# 2_FPGA.net
KiCad netlist of a schematic drawn in Altium Designer
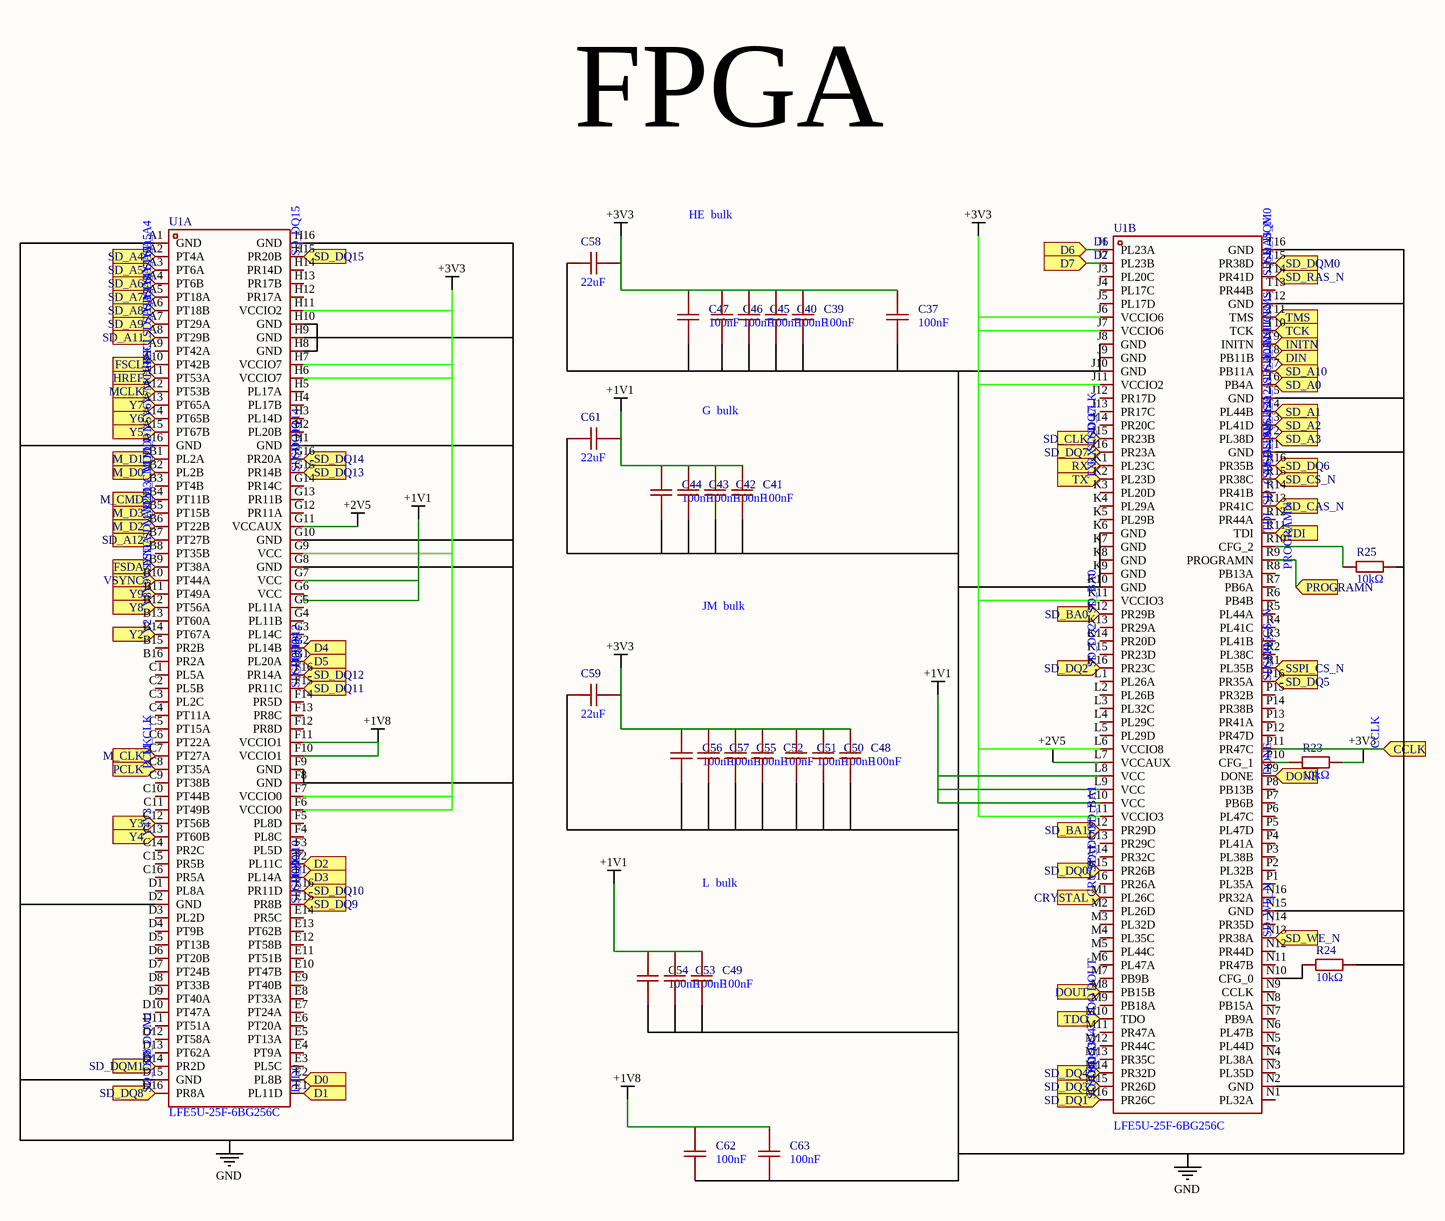
[diagram p0: 2_FPGA.schdoc]

(export (version "E")
  (design (tool "Eeschema 10.0.6"))
  (components
    (comp (ref "C37")
      (value "100nF")
      (footprint "C01005")
      (fields
        (field (name "MANUFACTURER") "muRata(村田)")
        (field (name "MANUFACTURER PART") "GRM022R60J104KE15D")
        (field (name "TOLERANCE") "±10%")
      )
      (libsource (lib "altium-import") (part "root_2_GRM022R60J104KE15D_"))
    )
    (comp (ref "C39")
      (value "100nF")
      (footprint "C01005")
      (fields
        (field (name "MANUFACTURER") "muRata(村田)")
        (field (name "MANUFACTURER PART") "GRM022R60J104KE15D")
        (field (name "TOLERANCE") "±10%")
      )
      (libsource (lib "altium-import") (part "root_2_GRM022R60J104KE15D_"))
    )
    (comp (ref "C40")
      (value "100nF")
      (footprint "C01005")
      (fields
        (field (name "MANUFACTURER") "muRata(村田)")
        (field (name "MANUFACTURER PART") "GRM022R60J104KE15D")
        (field (name "TOLERANCE") "±10%")
      )
      (libsource (lib "altium-import") (part "root_2_GRM022R60J104KE15D_"))
    )
    (comp (ref "C41")
      (value "100nF")
      (footprint "C01005")
      (fields
        (field (name "MANUFACTURER") "muRata(村田)")
        (field (name "MANUFACTURER PART") "GRM022R60J104KE15D")
        (field (name "TOLERANCE") "±10%")
      )
      (libsource (lib "altium-import") (part "root_2_GRM022R60J104KE15D_"))
    )
    (comp (ref "C42")
      (value "100nF")
      (footprint "C01005")
      (fields
        (field (name "MANUFACTURER") "muRata(村田)")
        (field (name "MANUFACTURER PART") "GRM022R60J104KE15D")
        (field (name "TOLERANCE") "±10%")
      )
      (libsource (lib "altium-import") (part "root_2_GRM022R60J104KE15D_"))
    )
    (comp (ref "C43")
      (value "100nF")
      (footprint "C01005")
      (fields
        (field (name "MANUFACTURER") "muRata(村田)")
        (field (name "MANUFACTURER PART") "GRM022R60J104KE15D")
        (field (name "TOLERANCE") "±10%")
      )
      (libsource (lib "altium-import") (part "root_2_GRM022R60J104KE15D_"))
    )
    (comp (ref "C44")
      (value "100nF")
      (footprint "C01005")
      (fields
        (field (name "MANUFACTURER") "muRata(村田)")
        (field (name "MANUFACTURER PART") "GRM022R60J104KE15D")
        (field (name "TOLERANCE") "±10%")
      )
      (libsource (lib "altium-import") (part "root_2_GRM022R60J104KE15D_"))
    )
    (comp (ref "C45")
      (value "100nF")
      (footprint "C01005")
      (fields
        (field (name "MANUFACTURER") "muRata(村田)")
        (field (name "MANUFACTURER PART") "GRM022R60J104KE15D")
        (field (name "TOLERANCE") "±10%")
      )
      (libsource (lib "altium-import") (part "root_2_GRM022R60J104KE15D_"))
    )
    (comp (ref "C46")
      (value "100nF")
      (footprint "C01005")
      (fields
        (field (name "MANUFACTURER") "muRata(村田)")
        (field (name "MANUFACTURER PART") "GRM022R60J104KE15D")
        (field (name "TOLERANCE") "±10%")
      )
      (libsource (lib "altium-import") (part "root_2_GRM022R60J104KE15D_"))
    )
    (comp (ref "C47")
      (value "100nF")
      (footprint "C01005")
      (fields
        (field (name "MANUFACTURER") "muRata(村田)")
        (field (name "MANUFACTURER PART") "GRM022R60J104KE15D")
        (field (name "TOLERANCE") "±10%")
      )
      (libsource (lib "altium-import") (part "root_2_GRM022R60J104KE15D_"))
    )
    (comp (ref "C48")
      (value "100nF")
      (footprint "C01005")
      (fields
        (field (name "MANUFACTURER") "muRata(村田)")
        (field (name "MANUFACTURER PART") "GRM022R60J104KE15D")
        (field (name "TOLERANCE") "±10%")
      )
      (libsource (lib "altium-import") (part "root_2_GRM022R60J104KE15D_"))
    )
    (comp (ref "C49")
      (value "100nF")
      (footprint "C01005")
      (fields
        (field (name "MANUFACTURER") "muRata(村田)")
        (field (name "MANUFACTURER PART") "GRM022R60J104KE15D")
        (field (name "TOLERANCE") "±10%")
      )
      (libsource (lib "altium-import") (part "root_2_GRM022R60J104KE15D_"))
    )
    (comp (ref "C50")
      (value "100nF")
      (footprint "C01005")
      (fields
        (field (name "MANUFACTURER") "muRata(村田)")
        (field (name "MANUFACTURER PART") "GRM022R60J104KE15D")
        (field (name "TOLERANCE") "±10%")
      )
      (libsource (lib "altium-import") (part "root_2_GRM022R60J104KE15D_"))
    )
    (comp (ref "C51")
      (value "100nF")
      (footprint "C01005")
      (fields
        (field (name "MANUFACTURER") "muRata(村田)")
        (field (name "MANUFACTURER PART") "GRM022R60J104KE15D")
        (field (name "TOLERANCE") "±10%")
      )
      (libsource (lib "altium-import") (part "root_2_GRM022R60J104KE15D_"))
    )
    (comp (ref "C52")
      (value "100nF")
      (footprint "C01005")
      (fields
        (field (name "MANUFACTURER") "muRata(村田)")
        (field (name "MANUFACTURER PART") "GRM022R60J104KE15D")
        (field (name "TOLERANCE") "±10%")
      )
      (libsource (lib "altium-import") (part "root_2_GRM022R60J104KE15D_"))
    )
    (comp (ref "C53")
      (value "100nF")
      (footprint "C01005")
      (fields
        (field (name "MANUFACTURER") "muRata(村田)")
        (field (name "MANUFACTURER PART") "GRM022R60J104KE15D")
        (field (name "TOLERANCE") "±10%")
      )
      (libsource (lib "altium-import") (part "root_2_GRM022R60J104KE15D_"))
    )
    (comp (ref "C54")
      (value "100nF")
      (footprint "C01005")
      (fields
        (field (name "MANUFACTURER") "muRata(村田)")
        (field (name "MANUFACTURER PART") "GRM022R60J104KE15D")
        (field (name "TOLERANCE") "±10%")
      )
      (libsource (lib "altium-import") (part "root_2_GRM022R60J104KE15D_"))
    )
    (comp (ref "C55")
      (value "100nF")
      (footprint "C01005")
      (fields
        (field (name "MANUFACTURER") "muRata(村田)")
        (field (name "MANUFACTURER PART") "GRM022R60J104KE15D")
        (field (name "TOLERANCE") "±10%")
      )
      (libsource (lib "altium-import") (part "root_2_GRM022R60J104KE15D_"))
    )
    (comp (ref "C56")
      (value "100nF")
      (footprint "C01005")
      (fields
        (field (name "MANUFACTURER") "muRata(村田)")
        (field (name "MANUFACTURER PART") "GRM022R60J104KE15D")
        (field (name "TOLERANCE") "±10%")
      )
      (libsource (lib "altium-import") (part "root_2_GRM022R60J104KE15D_"))
    )
    (comp (ref "C57")
      (value "100nF")
      (footprint "C01005")
      (fields
        (field (name "MANUFACTURER") "muRata(村田)")
        (field (name "MANUFACTURER PART") "GRM022R60J104KE15D")
        (field (name "TOLERANCE") "±10%")
      )
      (libsource (lib "altium-import") (part "root_2_GRM022R60J104KE15D_"))
    )
    (comp (ref "C58")
      (value "22uF")
      (footprint "C0603")
      (fields
        (field (name "MANUFACTURER") "CCTC(三环)")
        (field (name "MANUFACTURER PART") "TCC0603X5R226M6R3CT")
        (field (name "TOLERANCE") "±20%")
      )
      (libsource (lib "altium-import") (part "root_1_TCC0603X5R226M6R3CT_"))
    )
    (comp (ref "C59")
      (value "22uF")
      (footprint "C0603")
      (fields
        (field (name "MANUFACTURER") "CCTC(三环)")
        (field (name "MANUFACTURER PART") "TCC0603X5R226M6R3CT")
        (field (name "TOLERANCE") "±20%")
      )
      (libsource (lib "altium-import") (part "root_1_TCC0603X5R226M6R3CT_"))
    )
    (comp (ref "C61")
      (value "22uF")
      (footprint "C0603")
      (fields
        (field (name "MANUFACTURER") "CCTC(三环)")
        (field (name "MANUFACTURER PART") "TCC0603X5R226M6R3CT")
        (field (name "TOLERANCE") "±20%")
      )
      (libsource (lib "altium-import") (part "root_1_TCC0603X5R226M6R3CT_"))
    )
    (comp (ref "C62")
      (value "100nF")
      (footprint "C01005")
      (fields
        (field (name "MANUFACTURER") "muRata(村田)")
        (field (name "MANUFACTURER PART") "GRM022R60J104KE15D")
        (field (name "TOLERANCE") "±10%")
      )
      (libsource (lib "altium-import") (part "root_2_GRM022R60J104KE15D_"))
    )
    (comp (ref "C63")
      (value "100nF")
      (footprint "C01005")
      (fields
        (field (name "MANUFACTURER") "muRata(村田)")
        (field (name "MANUFACTURER PART") "GRM022R60J104KE15D")
        (field (name "TOLERANCE") "±10%")
      )
      (libsource (lib "altium-import") (part "root_2_GRM022R60J104KE15D_"))
    )
    (comp (ref "R23")
      (value "10kΩ")
      (footprint "R0402")
      (fields
        (field (name "MANUFACTURER") "UNI-ROYAL(厚声)")
        (field (name "MANUFACTURER PART") "0402WGF1002TCE")
        (field (name "TOLERANCE") "±1%")
      )
      (libsource (lib "altium-import") (part "root_2_0402WGF1002TCE_"))
    )
    (comp (ref "R24")
      (value "10kΩ")
      (footprint "R0402")
      (fields
        (field (name "MANUFACTURER") "UNI-ROYAL(厚声)")
        (field (name "MANUFACTURER PART") "0402WGF1002TCE")
        (field (name "TOLERANCE") "±1%")
      )
      (libsource (lib "altium-import") (part "root_2_0402WGF1002TCE_"))
    )
    (comp (ref "R25")
      (value "10kΩ")
      (footprint "R0402")
      (fields
        (field (name "MANUFACTURER") "UNI-ROYAL(厚声)")
        (field (name "MANUFACTURER PART") "0402WGF1002TCE")
        (field (name "TOLERANCE") "±1%")
      )
      (libsource (lib "altium-import") (part "root_2_0402WGF1002TCE_"))
    )
    (comp (ref "U1")
      (value "LFE5U-25F-6BG256C")
      (footprint "CABGA-256_L14.0-W14.0-R16-C16-P0.80-TL")
      (fields (field (name "MANUFACTURER") "LATTICE(莱迪思)"))
      (libsource (lib "altium-import") (part "root_0_LFE5U-25F-6BG256C_"))
    )
  )
  (nets
    (net (code "1") (name "+1V1") (class "Default")
      (node (ref "C41") (pin "1") (pinfunction "1_1") (pintype "passive"))
      (node (ref "C42") (pin "1") (pinfunction "1_1") (pintype "passive"))
      (node (ref "C43") (pin "1") (pinfunction "1_1") (pintype "passive"))
      (node (ref "C44") (pin "1") (pinfunction "1_1") (pintype "passive"))
      (node (ref "C49") (pin "1") (pinfunction "1_1") (pintype "passive"))
      (node (ref "C53") (pin "1") (pinfunction "1_1") (pintype "passive"))
      (node (ref "C54") (pin "1") (pinfunction "1_1") (pintype "passive"))
      (node (ref "C61") (pin "1") (pinfunction "1_1") (pintype "passive"))
      (node (ref "U1") (pin "G6") (pinfunction "VCC_G6") (pintype "passive"))
      (node (ref "U1") (pin "G7") (pinfunction "VCC_G7") (pintype "passive"))
      (node (ref "U1") (pin "L10") (pinfunction "VCC_L10") (pintype "passive"))
      (node (ref "U1") (pin "L8") (pinfunction "VCC_L8") (pintype "passive"))
      (node (ref "U1") (pin "L9") (pinfunction "VCC_L9") (pintype "passive"))
    )
    (net (code "2") (name "+1V8") (class "Default")
      (node (ref "C62") (pin "1") (pinfunction "1_1") (pintype "passive"))
      (node (ref "C63") (pin "1") (pinfunction "1_1") (pintype "passive"))
      (node (ref "U1") (pin "F10") (pinfunction "VCCIO1_F10") (pintype "passive"))
      (node (ref "U1") (pin "F11") (pinfunction "VCCIO1_F11") (pintype "passive"))
    )
    (net (code "3") (name "+2V5") (class "Default")
      (node (ref "U1") (pin "G11") (pinfunction "VCCAUX_G11") (pintype "passive"))
      (node (ref "U1") (pin "L7") (pinfunction "VCCAUX_L7") (pintype "passive"))
    )
    (net (code "4") (name "+3V3") (class "Default")
      (node (ref "C37") (pin "1") (pinfunction "1_1") (pintype "passive"))
      (node (ref "C39") (pin "1") (pinfunction "1_1") (pintype "passive"))
      (node (ref "C40") (pin "1") (pinfunction "1_1") (pintype "passive"))
      (node (ref "C45") (pin "1") (pinfunction "1_1") (pintype "passive"))
      (node (ref "C46") (pin "1") (pinfunction "1_1") (pintype "passive"))
      (node (ref "C47") (pin "1") (pinfunction "1_1") (pintype "passive"))
      (node (ref "C48") (pin "1") (pinfunction "1_1") (pintype "passive"))
      (node (ref "C50") (pin "1") (pinfunction "1_1") (pintype "passive"))
      (node (ref "C51") (pin "1") (pinfunction "1_1") (pintype "passive"))
      (node (ref "C52") (pin "1") (pinfunction "1_1") (pintype "passive"))
      (node (ref "C55") (pin "1") (pinfunction "1_1") (pintype "passive"))
      (node (ref "C56") (pin "1") (pinfunction "1_1") (pintype "passive"))
      (node (ref "C57") (pin "1") (pinfunction "1_1") (pintype "passive"))
      (node (ref "C58") (pin "1") (pinfunction "1_1") (pintype "passive"))
      (node (ref "C59") (pin "1") (pinfunction "1_1") (pintype "passive"))
      (node (ref "R23") (pin "1") (pinfunction "1_1") (pintype "passive"))
      (node (ref "U1") (pin "F6") (pinfunction "VCCIO0_F6") (pintype "passive"))
      (node (ref "U1") (pin "F7") (pinfunction "VCCIO0_F7") (pintype "passive"))
      (node (ref "U1") (pin "G9") (pinfunction "VCC_G9") (pintype "passive"))
      (node (ref "U1") (pin "H11") (pinfunction "VCCIO2_H11") (pintype "passive"))
      (node (ref "U1") (pin "H6") (pinfunction "VCCIO7_H6") (pintype "passive"))
      (node (ref "U1") (pin "H7") (pinfunction "VCCIO7_H7") (pintype "passive"))
      (node (ref "U1") (pin "J11") (pinfunction "VCCIO2_J11") (pintype "passive"))
      (node (ref "U1") (pin "J6") (pinfunction "VCCIO6_J6") (pintype "passive"))
      (node (ref "U1") (pin "J7") (pinfunction "VCCIO6_J7") (pintype "passive"))
      (node (ref "U1") (pin "K11") (pinfunction "VCCIO3_K11") (pintype "passive"))
      (node (ref "U1") (pin "L11") (pinfunction "VCCIO3_L11") (pintype "passive"))
      (node (ref "U1") (pin "L6") (pinfunction "VCCIO8_L6") (pintype "passive"))
    )
    (net (code "5") (name "/CCLK") (class "Default")
      (node (ref "U1") (pin "P11") (pinfunction "PR47C_P11") (pintype "passive"))
    )
    (net (code "6") (name "/CRYSTAL") (class "Default")
      (node (ref "U1") (pin "M1") (pinfunction "PL26C_M1") (pintype "passive"))
    )
    (net (code "7") (name "/D0") (class "Default")
      (node (ref "U1") (pin "E2") (pinfunction "PL8B_E2") (pintype "passive"))
    )
    (net (code "8") (name "/D1") (class "Default")
      (node (ref "U1") (pin "E1") (pinfunction "PL11D_E1") (pintype "passive"))
    )
    (net (code "9") (name "/D2") (class "Default")
      (node (ref "U1") (pin "F2") (pinfunction "PL11C_F2") (pintype "passive"))
    )
    (net (code "10") (name "/D3") (class "Default")
      (node (ref "U1") (pin "F1") (pinfunction "PL14A_F1") (pintype "passive"))
    )
    (net (code "11") (name "/D4") (class "Default")
      (node (ref "U1") (pin "G2") (pinfunction "PL14B_G2") (pintype "passive"))
    )
    (net (code "12") (name "/D5") (class "Default")
      (node (ref "U1") (pin "G1") (pinfunction "PL20A_G1") (pintype "passive"))
    )
    (net (code "13") (name "/D6") (class "Default")
      (node (ref "U1") (pin "J1") (pinfunction "PL23A_J1") (pintype "passive"))
    )
    (net (code "14") (name "/D7") (class "Default")
      (node (ref "U1") (pin "J2") (pinfunction "PL23B_J2") (pintype "passive"))
    )
    (net (code "15") (name "/DIN") (class "Default")
      (node (ref "U1") (pin "T8") (pinfunction "PB11B_T8") (pintype "passive"))
    )
    (net (code "16") (name "/DONE") (class "Default")
      (node (ref "U1") (pin "P9") (pinfunction "DONE_P9") (pintype "passive"))
    )
    (net (code "17") (name "/DOUT") (class "Default")
      (node (ref "U1") (pin "M8") (pinfunction "PB15B_M8") (pintype "passive"))
    )
    (net (code "18") (name "/FSCL") (class "Default")
      (node (ref "U1") (pin "A10") (pinfunction "PT42B_A10") (pintype "passive"))
    )
    (net (code "19") (name "/FSDA") (class "Default")
      (node (ref "U1") (pin "B9") (pinfunction "PT38A_B9") (pintype "passive"))
    )
    (net (code "20") (name "/HREF") (class "Default")
      (node (ref "U1") (pin "A11") (pinfunction "PT53A_A11") (pintype "passive"))
    )
    (net (code "21") (name "/INITN") (class "Default")
      (node (ref "U1") (pin "T9") (pinfunction "INITN_T9") (pintype "passive"))
    )
    (net (code "22") (name "/MCLK") (class "Default")
      (node (ref "U1") (pin "A12") (pinfunction "PT53B_A12") (pintype "passive"))
    )
    (net (code "23") (name "/M_CLK") (class "Default")
      (node (ref "U1") (pin "C7") (pinfunction "PT27A_C7") (pintype "passive"))
    )
    (net (code "24") (name "/M_CMD") (class "Default")
      (node (ref "U1") (pin "B4") (pinfunction "PT11B_B4") (pintype "passive"))
    )
    (net (code "25") (name "/M_D0") (class "Default")
      (node (ref "U1") (pin "B2") (pinfunction "PL2B_B2") (pintype "passive"))
    )
    (net (code "26") (name "/M_D1") (class "Default")
      (node (ref "U1") (pin "B1") (pinfunction "PL2A_B1") (pintype "passive"))
    )
    (net (code "27") (name "/M_D2") (class "Default")
      (node (ref "U1") (pin "B6") (pinfunction "PT22B_B6") (pintype "passive"))
    )
    (net (code "28") (name "/M_D3") (class "Default")
      (node (ref "U1") (pin "B5") (pinfunction "PT15B_B5") (pintype "passive"))
    )
    (net (code "29") (name "/PCLK") (class "Default")
      (node (ref "U1") (pin "C8") (pinfunction "PT35A_C8") (pintype "passive"))
    )
    (net (code "30") (name "/PROGRAMN") (class "Default")
      (node (ref "U1") (pin "R9") (pinfunction "PROGRAMN_R9") (pintype "passive"))
    )
    (net (code "31") (name "/RX") (class "Default")
      (node (ref "U1") (pin "K1") (pinfunction "PL23C_K1") (pintype "passive"))
    )
    (net (code "32") (name "/SD_A0") (class "Default")
      (node (ref "U1") (pin "T6") (pinfunction "PB4A_T6") (pintype "passive"))
    )
    (net (code "33") (name "/SD_A1") (class "Default")
      (node (ref "U1") (pin "T4") (pinfunction "PL44B_T4") (pintype "passive"))
    )
    (net (code "34") (name "/SD_A2") (class "Default")
      (node (ref "U1") (pin "T3") (pinfunction "PL41D_T3") (pintype "passive"))
    )
    (net (code "35") (name "/SD_A3") (class "Default")
      (node (ref "U1") (pin "T2") (pinfunction "PL38D_T2") (pintype "passive"))
    )
    (net (code "36") (name "/SD_A4") (class "Default")
      (node (ref "U1") (pin "A2") (pinfunction "PT4A_A2") (pintype "passive"))
    )
    (net (code "37") (name "/SD_A5") (class "Default")
      (node (ref "U1") (pin "A3") (pinfunction "PT6A_A3") (pintype "passive"))
    )
    (net (code "38") (name "/SD_A6") (class "Default")
      (node (ref "U1") (pin "A4") (pinfunction "PT6B_A4") (pintype "passive"))
    )
    (net (code "39") (name "/SD_A7") (class "Default")
      (node (ref "U1") (pin "A5") (pinfunction "PT18A_A5") (pintype "passive"))
    )
    (net (code "40") (name "/SD_A8") (class "Default")
      (node (ref "U1") (pin "A6") (pinfunction "PT18B_A6") (pintype "passive"))
    )
    (net (code "41") (name "/SD_A9") (class "Default")
      (node (ref "U1") (pin "A7") (pinfunction "PT29A_A7") (pintype "passive"))
    )
    (net (code "42") (name "/SD_A10") (class "Default")
      (node (ref "U1") (pin "T7") (pinfunction "PB11A_T7") (pintype "passive"))
    )
    (net (code "43") (name "/SD_A11") (class "Default")
      (node (ref "U1") (pin "A8") (pinfunction "PT29B_A8") (pintype "passive"))
    )
    (net (code "44") (name "/SD_A12") (class "Default")
      (node (ref "U1") (pin "B7") (pinfunction "PT27B_B7") (pintype "passive"))
    )
    (net (code "45") (name "/SD_BA0") (class "Default")
      (node (ref "U1") (pin "K12") (pinfunction "PR29B_K12") (pintype "passive"))
    )
    (net (code "46") (name "/SD_BA1") (class "Default")
      (node (ref "U1") (pin "L12") (pinfunction "PR29D_L12") (pintype "passive"))
    )
    (net (code "47") (name "/SD_CAS_N") (class "Default")
      (node (ref "U1") (pin "R13") (pinfunction "PR41C_R13") (pintype "passive"))
    )
    (net (code "48") (name "/SD_CLK") (class "Default")
      (node (ref "U1") (pin "J15") (pinfunction "PR23B_J15") (pintype "passive"))
    )
    (net (code "49") (name "/SD_CS_N") (class "Default")
      (node (ref "U1") (pin "R15") (pinfunction "PR38C_R15") (pintype "passive"))
    )
    (net (code "50") (name "/SD_DQ0") (class "Default")
      (node (ref "U1") (pin "L15") (pinfunction "PR26B_L15") (pintype "passive"))
    )
    (net (code "51") (name "/SD_DQ1") (class "Default")
      (node (ref "U1") (pin "M16") (pinfunction "PR26C_M16") (pintype "passive"))
    )
    (net (code "52") (name "/SD_DQ2") (class "Default")
      (node (ref "U1") (pin "K16") (pinfunction "PR23C_K16") (pintype "passive"))
    )
    (net (code "53") (name "/SD_DQ3") (class "Default")
      (node (ref "U1") (pin "M15") (pinfunction "PR26D_M15") (pintype "passive"))
    )
    (net (code "54") (name "/SD_DQ4") (class "Default")
      (node (ref "U1") (pin "M14") (pinfunction "PR32D_M14") (pintype "passive"))
    )
    (net (code "55") (name "/SD_DQ5") (class "Default")
      (node (ref "U1") (pin "P16") (pinfunction "PR35A_P16") (pintype "passive"))
    )
    (net (code "56") (name "/SD_DQ6") (class "Default")
      (node (ref "U1") (pin "R16") (pinfunction "PR35B_R16") (pintype "passive"))
    )
    (net (code "57") (name "/SD_DQ7") (class "Default")
      (node (ref "U1") (pin "J16") (pinfunction "PR23A_J16") (pintype "passive"))
    )
    (net (code "58") (name "/SD_DQ8") (class "Default")
      (node (ref "U1") (pin "D16") (pinfunction "PR8A_D16") (pintype "passive"))
    )
    (net (code "59") (name "/SD_DQ9") (class "Default")
      (node (ref "U1") (pin "E15") (pinfunction "PR8B_E15") (pintype "passive"))
    )
    (net (code "60") (name "/SD_DQ10") (class "Default")
      (node (ref "U1") (pin "E16") (pinfunction "PR11D_E16") (pintype "passive"))
    )
    (net (code "61") (name "/SD_DQ11") (class "Default")
      (node (ref "U1") (pin "F15") (pinfunction "PR11C_F15") (pintype "passive"))
    )
    (net (code "62") (name "/SD_DQ12") (class "Default")
      (node (ref "U1") (pin "F16") (pinfunction "PR14A_F16") (pintype "passive"))
    )
    (net (code "63") (name "/SD_DQ13") (class "Default")
      (node (ref "U1") (pin "G15") (pinfunction "PR14B_G15") (pintype "passive"))
    )
    (net (code "64") (name "/SD_DQ14") (class "Default")
      (node (ref "U1") (pin "G16") (pinfunction "PR20A_G16") (pintype "passive"))
    )
    (net (code "65") (name "/SD_DQ15") (class "Default")
      (node (ref "U1") (pin "H15") (pinfunction "PR20B_H15") (pintype "passive"))
    )
    (net (code "66") (name "/SD_DQM0") (class "Default")
      (node (ref "U1") (pin "T15") (pinfunction "PR38D_T15") (pintype "passive"))
    )
    (net (code "67") (name "/SD_DQM1") (class "Default")
      (node (ref "U1") (pin "D14") (pinfunction "PR2D_D14") (pintype "passive"))
    )
    (net (code "68") (name "/SD_RAS_N") (class "Default")
      (node (ref "U1") (pin "T14") (pinfunction "PR41D_T14") (pintype "passive"))
    )
    (net (code "69") (name "/SD_WE_N") (class "Default")
      (node (ref "U1") (pin "N13") (pinfunction "PR38A_N13") (pintype "passive"))
    )
    (net (code "70") (name "/SSPI_CS_N") (class "Default")
      (node (ref "U1") (pin "R1") (pinfunction "PL35B_R1") (pintype "passive"))
    )
    (net (code "71") (name "/TCK") (class "Default")
      (node (ref "U1") (pin "T10") (pinfunction "TCK_T10") (pintype "passive"))
    )
    (net (code "72") (name "/TDI") (class "Default")
      (node (ref "U1") (pin "R11") (pinfunction "TDI_R11") (pintype "passive"))
    )
    (net (code "73") (name "/TDO") (class "Default")
      (node (ref "U1") (pin "M10") (pinfunction "TDO_M10") (pintype "passive"))
    )
    (net (code "74") (name "/TMS") (class "Default")
      (node (ref "U1") (pin "T11") (pinfunction "TMS_T11") (pintype "passive"))
    )
    (net (code "75") (name "/TX") (class "Default")
      (node (ref "U1") (pin "K2") (pinfunction "PL23D_K2") (pintype "passive"))
    )
    (net (code "76") (name "/VSYNC") (class "Default")
      (node (ref "U1") (pin "B10") (pinfunction "PT44A_B10") (pintype "passive"))
    )
    (net (code "77") (name "/Y2") (class "Default")
      (node (ref "U1") (pin "B14") (pinfunction "PT67A_B14") (pintype "passive"))
    )
    (net (code "78") (name "/Y3") (class "Default")
      (node (ref "U1") (pin "C12") (pinfunction "PT56B_C12") (pintype "passive"))
    )
    (net (code "79") (name "/Y4") (class "Default")
      (node (ref "U1") (pin "C13") (pinfunction "PT60B_C13") (pintype "passive"))
    )
    (net (code "80") (name "/Y5") (class "Default")
      (node (ref "U1") (pin "A15") (pinfunction "PT67B_A15") (pintype "passive"))
    )
    (net (code "81") (name "/Y6") (class "Default")
      (node (ref "U1") (pin "A14") (pinfunction "PT65B_A14") (pintype "passive"))
    )
    (net (code "82") (name "/Y7") (class "Default")
      (node (ref "U1") (pin "A13") (pinfunction "PT65A_A13") (pintype "passive"))
    )
    (net (code "83") (name "/Y8") (class "Default")
      (node (ref "U1") (pin "B12") (pinfunction "PT56A_B12") (pintype "passive"))
    )
    (net (code "84") (name "/Y9") (class "Default")
      (node (ref "U1") (pin "B11") (pinfunction "PT49A_B11") (pintype "passive"))
    )
    (net (code "85") (name "GND") (class "Default")
      (node (ref "C37") (pin "2") (pinfunction "2_2") (pintype "passive"))
      (node (ref "C39") (pin "2") (pinfunction "2_2") (pintype "passive"))
      (node (ref "C40") (pin "2") (pinfunction "2_2") (pintype "passive"))
      (node (ref "C41") (pin "2") (pinfunction "2_2") (pintype "passive"))
      (node (ref "C42") (pin "2") (pinfunction "2_2") (pintype "passive"))
      (node (ref "C43") (pin "2") (pinfunction "2_2") (pintype "passive"))
      (node (ref "C44") (pin "2") (pinfunction "2_2") (pintype "passive"))
      (node (ref "C45") (pin "2") (pinfunction "2_2") (pintype "passive"))
      (node (ref "C46") (pin "2") (pinfunction "2_2") (pintype "passive"))
      (node (ref "C47") (pin "2") (pinfunction "2_2") (pintype "passive"))
      (node (ref "C48") (pin "2") (pinfunction "2_2") (pintype "passive"))
      (node (ref "C49") (pin "2") (pinfunction "2_2") (pintype "passive"))
      (node (ref "C50") (pin "2") (pinfunction "2_2") (pintype "passive"))
      (node (ref "C51") (pin "2") (pinfunction "2_2") (pintype "passive"))
      (node (ref "C52") (pin "2") (pinfunction "2_2") (pintype "passive"))
      (node (ref "C53") (pin "2") (pinfunction "2_2") (pintype "passive"))
      (node (ref "C54") (pin "2") (pinfunction "2_2") (pintype "passive"))
      (node (ref "C55") (pin "2") (pinfunction "2_2") (pintype "passive"))
      (node (ref "C56") (pin "2") (pinfunction "2_2") (pintype "passive"))
      (node (ref "C57") (pin "2") (pinfunction "2_2") (pintype "passive"))
      (node (ref "C58") (pin "2") (pinfunction "2_2") (pintype "passive"))
      (node (ref "C59") (pin "2") (pinfunction "2_2") (pintype "passive"))
      (node (ref "C61") (pin "2") (pinfunction "2_2") (pintype "passive"))
      (node (ref "C62") (pin "2") (pinfunction "2_2") (pintype "passive"))
      (node (ref "C63") (pin "2") (pinfunction "2_2") (pintype "passive"))
      (node (ref "R24") (pin "1") (pinfunction "1_1") (pintype "passive"))
      (node (ref "R25") (pin "1") (pinfunction "1_1") (pintype "passive"))
      (node (ref "U1") (pin "A1") (pinfunction "GND_A1") (pintype "passive"))
      (node (ref "U1") (pin "A16") (pinfunction "GND_A16") (pintype "passive"))
      (node (ref "U1") (pin "D15") (pinfunction "GND_D15") (pintype "passive"))
      (node (ref "U1") (pin "D2") (pinfunction "GND_D2") (pintype "passive"))
      (node (ref "U1") (pin "F8") (pinfunction "GND_F8") (pintype "passive"))
      (node (ref "U1") (pin "F9") (pinfunction "GND_F9") (pintype "passive"))
      (node (ref "U1") (pin "G10") (pinfunction "GND_G10") (pintype "passive"))
      (node (ref "U1") (pin "G8") (pinfunction "GND_G8") (pintype "passive"))
      (node (ref "U1") (pin "H1") (pinfunction "GND_H1") (pintype "passive"))
      (node (ref "U1") (pin "H10") (pinfunction "GND_H10") (pintype "passive"))
      (node (ref "U1") (pin "H16") (pinfunction "GND_H16") (pintype "passive"))
      (node (ref "U1") (pin "H8") (pinfunction "GND_H8") (pintype "passive"))
      (node (ref "U1") (pin "H9") (pinfunction "GND_H9") (pintype "passive"))
      (node (ref "U1") (pin "J10") (pinfunction "GND_J10") (pintype "passive"))
      (node (ref "U1") (pin "J8") (pinfunction "GND_J8") (pintype "passive"))
      (node (ref "U1") (pin "J9") (pinfunction "GND_J9") (pintype "passive"))
      (node (ref "U1") (pin "K10") (pinfunction "GND_K10") (pintype "passive"))
      (node (ref "U1") (pin "K6") (pinfunction "GND_K6") (pintype "passive"))
      (node (ref "U1") (pin "K7") (pinfunction "GND_K7") (pintype "passive"))
      (node (ref "U1") (pin "K8") (pinfunction "GND_K8") (pintype "passive"))
      (node (ref "U1") (pin "K9") (pinfunction "GND_K9") (pintype "passive"))
      (node (ref "U1") (pin "N15") (pinfunction "GND_N15") (pintype "passive"))
      (node (ref "U1") (pin "N2") (pinfunction "GND_N2") (pintype "passive"))
      (node (ref "U1") (pin "T1") (pinfunction "GND_T1") (pintype "passive"))
      (node (ref "U1") (pin "T12") (pinfunction "GND_T12") (pintype "passive"))
      (node (ref "U1") (pin "T16") (pinfunction "GND_T16") (pintype "passive"))
      (node (ref "U1") (pin "T5") (pinfunction "GND_T5") (pintype "passive"))
    )
    (net (code "86") (name "Net-(U1B-CFG_0)") (class "Default")
      (node (ref "R24") (pin "2") (pinfunction "2_2") (pintype "passive"))
      (node (ref "U1") (pin "N10") (pinfunction "CFG_0_N10") (pintype "passive"))
    )
    (net (code "87") (name "Net-(U1B-CFG_1)") (class "Default")
      (node (ref "R23") (pin "2") (pinfunction "2_2") (pintype "passive"))
      (node (ref "U1") (pin "P10") (pinfunction "CFG_1_P10") (pintype "passive"))
    )
    (net (code "88") (name "Net-(U1B-CFG_2)") (class "Default")
      (node (ref "R25") (pin "2") (pinfunction "2_2") (pintype "passive"))
      (node (ref "U1") (pin "R10") (pinfunction "CFG_2_R10") (pintype "passive"))
    )
    (net (code "89") (name "unconnected-(U1A-PL2C-PadC3)") (class "Default")
      (node (ref "U1") (pin "C3") (pinfunction "PL2C_C3") (pintype "passive"))
    )
    (net (code "90") (name "unconnected-(U1A-PL2D-PadD3)") (class "Default")
      (node (ref "U1") (pin "D3") (pinfunction "PL2D_D3") (pintype "passive"))
    )
    (net (code "91") (name "unconnected-(U1A-PL5A-PadC1)") (class "Default")
      (node (ref "U1") (pin "C1") (pinfunction "PL5A_C1") (pintype "passive"))
    )
    (net (code "92") (name "unconnected-(U1A-PL5B-PadC2)") (class "Default")
      (node (ref "U1") (pin "C2") (pinfunction "PL5B_C2") (pintype "passive"))
    )
    (net (code "93") (name "unconnected-(U1A-PL5C-PadE3)") (class "Default")
      (node (ref "U1") (pin "E3") (pinfunction "PL5C_E3") (pintype "passive"))
    )
    (net (code "94") (name "unconnected-(U1A-PL5D-PadF3)") (class "Default")
      (node (ref "U1") (pin "F3") (pinfunction "PL5D_F3") (pintype "passive"))
    )
    (net (code "95") (name "unconnected-(U1A-PL8A-PadD1)") (class "Default")
      (node (ref "U1") (pin "D1") (pinfunction "PL8A_D1") (pintype "passive"))
    )
    (net (code "96") (name "unconnected-(U1A-PL8C-PadF4)") (class "Default")
      (node (ref "U1") (pin "F4") (pinfunction "PL8C_F4") (pintype "passive"))
    )
    (net (code "97") (name "unconnected-(U1A-PL8D-PadF5)") (class "Default")
      (node (ref "U1") (pin "F5") (pinfunction "PL8D_F5") (pintype "passive"))
    )
    (net (code "98") (name "unconnected-(U1A-PL11A-PadG5)") (class "Default")
      (node (ref "U1") (pin "G5") (pinfunction "PL11A_G5") (pintype "passive"))
    )
    (net (code "99") (name "unconnected-(U1A-PL11B-PadG4)") (class "Default")
      (node (ref "U1") (pin "G4") (pinfunction "PL11B_G4") (pintype "passive"))
    )
    (net (code "100") (name "unconnected-(U1A-PL14C-PadG3)") (class "Default")
      (node (ref "U1") (pin "G3") (pinfunction "PL14C_G3") (pintype "passive"))
    )
    (net (code "101") (name "unconnected-(U1A-PL14D-PadH3)") (class "Default")
      (node (ref "U1") (pin "H3") (pinfunction "PL14D_H3") (pintype "passive"))
    )
    (net (code "102") (name "unconnected-(U1A-PL17A-PadH5)") (class "Default")
      (node (ref "U1") (pin "H5") (pinfunction "PL17A_H5") (pintype "passive"))
    )
    (net (code "103") (name "unconnected-(U1A-PL17B-PadH4)") (class "Default")
      (node (ref "U1") (pin "H4") (pinfunction "PL17B_H4") (pintype "passive"))
    )
    (net (code "104") (name "unconnected-(U1A-PL20B-PadH2)") (class "Default")
      (node (ref "U1") (pin "H2") (pinfunction "PL20B_H2") (pintype "passive"))
    )
    (net (code "105") (name "unconnected-(U1A-PR2A-PadB16)") (class "Default")
      (node (ref "U1") (pin "B16") (pinfunction "PR2A_B16") (pintype "passive"))
    )
    (net (code "106") (name "unconnected-(U1A-PR2B-PadB15)") (class "Default")
      (node (ref "U1") (pin "B15") (pinfunction "PR2B_B15") (pintype "passive"))
    )
    (net (code "107") (name "unconnected-(U1A-PR2C-PadC14)") (class "Default")
      (node (ref "U1") (pin "C14") (pinfunction "PR2C_C14") (pintype "passive"))
    )
    (net (code "108") (name "unconnected-(U1A-PR5A-PadC16)") (class "Default")
      (node (ref "U1") (pin "C16") (pinfunction "PR5A_C16") (pintype "passive"))
    )
    (net (code "109") (name "unconnected-(U1A-PR5B-PadC15)") (class "Default")
      (node (ref "U1") (pin "C15") (pinfunction "PR5B_C15") (pintype "passive"))
    )
    (net (code "110") (name "unconnected-(U1A-PR5C-PadE14)") (class "Default")
      (node (ref "U1") (pin "E14") (pinfunction "PR5C_E14") (pintype "passive"))
    )
    (net (code "111") (name "unconnected-(U1A-PR5D-PadF14)") (class "Default")
      (node (ref "U1") (pin "F14") (pinfunction "PR5D_F14") (pintype "passive"))
    )
    (net (code "112") (name "unconnected-(U1A-PR8C-PadF13)") (class "Default")
      (node (ref "U1") (pin "F13") (pinfunction "PR8C_F13") (pintype "passive"))
    )
    (net (code "113") (name "unconnected-(U1A-PR8D-PadF12)") (class "Default")
      (node (ref "U1") (pin "F12") (pinfunction "PR8D_F12") (pintype "passive"))
    )
    (net (code "114") (name "unconnected-(U1A-PR11A-PadG12)") (class "Default")
      (node (ref "U1") (pin "G12") (pinfunction "PR11A_G12") (pintype "passive"))
    )
    (net (code "115") (name "unconnected-(U1A-PR11B-PadG13)") (class "Default")
      (node (ref "U1") (pin "G13") (pinfunction "PR11B_G13") (pintype "passive"))
    )
    (net (code "116") (name "unconnected-(U1A-PR14C-PadG14)") (class "Default")
      (node (ref "U1") (pin "G14") (pinfunction "PR14C_G14") (pintype "passive"))
    )
    (net (code "117") (name "unconnected-(U1A-PR14D-PadH14)") (class "Default")
      (node (ref "U1") (pin "H14") (pinfunction "PR14D_H14") (pintype "passive"))
    )
    (net (code "118") (name "unconnected-(U1A-PR17A-PadH12)") (class "Default")
      (node (ref "U1") (pin "H12") (pinfunction "PR17A_H12") (pintype "passive"))
    )
    (net (code "119") (name "unconnected-(U1A-PR17B-PadH13)") (class "Default")
      (node (ref "U1") (pin "H13") (pinfunction "PR17B_H13") (pintype "passive"))
    )
    (net (code "120") (name "unconnected-(U1A-PT4B-PadB3)") (class "Default")
      (node (ref "U1") (pin "B3") (pinfunction "PT4B_B3") (pintype "passive"))
    )
    (net (code "121") (name "unconnected-(U1A-PT9A-PadE4)") (class "Default")
      (node (ref "U1") (pin "E4") (pinfunction "PT9A_E4") (pintype "passive"))
    )
    (net (code "122") (name "unconnected-(U1A-PT9B-PadD4)") (class "Default")
      (node (ref "U1") (pin "D4") (pinfunction "PT9B_D4") (pintype "passive"))
    )
    (net (code "123") (name "unconnected-(U1A-PT11A-PadC4)") (class "Default")
      (node (ref "U1") (pin "C4") (pinfunction "PT11A_C4") (pintype "passive"))
    )
    (net (code "124") (name "unconnected-(U1A-PT13A-PadE5)") (class "Default")
      (node (ref "U1") (pin "E5") (pinfunction "PT13A_E5") (pintype "passive"))
    )
    (net (code "125") (name "unconnected-(U1A-PT13B-PadD5)") (class "Default")
      (node (ref "U1") (pin "D5") (pinfunction "PT13B_D5") (pintype "passive"))
    )
    (net (code "126") (name "unconnected-(U1A-PT15A-PadC5)") (class "Default")
      (node (ref "U1") (pin "C5") (pinfunction "PT15A_C5") (pintype "passive"))
    )
    (net (code "127") (name "unconnected-(U1A-PT20A-PadE6)") (class "Default")
      (node (ref "U1") (pin "E6") (pinfunction "PT20A_E6") (pintype "passive"))
    )
    (net (code "128") (name "unconnected-(U1A-PT20B-PadD6)") (class "Default")
      (node (ref "U1") (pin "D6") (pinfunction "PT20B_D6") (pintype "passive"))
    )
    (net (code "129") (name "unconnected-(U1A-PT22A-PadC6)") (class "Default")
      (node (ref "U1") (pin "C6") (pinfunction "PT22A_C6") (pintype "passive"))
    )
    (net (code "130") (name "unconnected-(U1A-PT24A-PadE7)") (class "Default")
      (node (ref "U1") (pin "E7") (pinfunction "PT24A_E7") (pintype "passive"))
    )
    (net (code "131") (name "unconnected-(U1A-PT24B-PadD7)") (class "Default")
      (node (ref "U1") (pin "D7") (pinfunction "PT24B_D7") (pintype "passive"))
    )
    (net (code "132") (name "unconnected-(U1A-PT33A-PadE8)") (class "Default")
      (node (ref "U1") (pin "E8") (pinfunction "PT33A_E8") (pintype "passive"))
    )
    (net (code "133") (name "unconnected-(U1A-PT33B-PadD8)") (class "Default")
      (node (ref "U1") (pin "D8") (pinfunction "PT33B_D8") (pintype "passive"))
    )
    (net (code "134") (name "unconnected-(U1A-PT35B-PadB8)") (class "Default")
      (node (ref "U1") (pin "B8") (pinfunction "PT35B_B8") (pintype "passive"))
    )
    (net (code "135") (name "unconnected-(U1A-PT38B-PadC9)") (class "Default")
      (node (ref "U1") (pin "C9") (pinfunction "PT38B_C9") (pintype "passive"))
    )
    (net (code "136") (name "unconnected-(U1A-PT40A-PadD9)") (class "Default")
      (node (ref "U1") (pin "D9") (pinfunction "PT40A_D9") (pintype "passive"))
    )
    (net (code "137") (name "unconnected-(U1A-PT40B-PadE9)") (class "Default")
      (node (ref "U1") (pin "E9") (pinfunction "PT40B_E9") (pintype "passive"))
    )
    (net (code "138") (name "unconnected-(U1A-PT42A-PadA9)") (class "Default")
      (node (ref "U1") (pin "A9") (pinfunction "PT42A_A9") (pintype "passive"))
    )
    (net (code "139") (name "unconnected-(U1A-PT44B-PadC10)") (class "Default")
      (node (ref "U1") (pin "C10") (pinfunction "PT44B_C10") (pintype "passive"))
    )
    (net (code "140") (name "unconnected-(U1A-PT47A-PadD10)") (class "Default")
      (node (ref "U1") (pin "D10") (pinfunction "PT47A_D10") (pintype "passive"))
    )
    (net (code "141") (name "unconnected-(U1A-PT47B-PadE10)") (class "Default")
      (node (ref "U1") (pin "E10") (pinfunction "PT47B_E10") (pintype "passive"))
    )
    (net (code "142") (name "unconnected-(U1A-PT49B-PadC11)") (class "Default")
      (node (ref "U1") (pin "C11") (pinfunction "PT49B_C11") (pintype "passive"))
    )
    (net (code "143") (name "unconnected-(U1A-PT51A-PadD11)") (class "Default")
      (node (ref "U1") (pin "D11") (pinfunction "PT51A_D11") (pintype "passive"))
    )
    (net (code "144") (name "unconnected-(U1A-PT51B-PadE11)") (class "Default")
      (node (ref "U1") (pin "E11") (pinfunction "PT51B_E11") (pintype "passive"))
    )
    (net (code "145") (name "unconnected-(U1A-PT58A-PadD12)") (class "Default")
      (node (ref "U1") (pin "D12") (pinfunction "PT58A_D12") (pintype "passive"))
    )
    (net (code "146") (name "unconnected-(U1A-PT58B-PadE12)") (class "Default")
      (node (ref "U1") (pin "E12") (pinfunction "PT58B_E12") (pintype "passive"))
    )
    (net (code "147") (name "unconnected-(U1A-PT60A-PadB13)") (class "Default")
      (node (ref "U1") (pin "B13") (pinfunction "PT60A_B13") (pintype "passive"))
    )
    (net (code "148") (name "unconnected-(U1A-PT62A-PadD13)") (class "Default")
      (node (ref "U1") (pin "D13") (pinfunction "PT62A_D13") (pintype "passive"))
    )
    (net (code "149") (name "unconnected-(U1A-PT62B-PadE13)") (class "Default")
      (node (ref "U1") (pin "E13") (pinfunction "PT62B_E13") (pintype "passive"))
    )
    (net (code "150") (name "unconnected-(U1B-CCLK-PadN9)") (class "Default")
      (node (ref "U1") (pin "N9") (pinfunction "CCLK_N9") (pintype "passive"))
    )
    (net (code "151") (name "unconnected-(U1B-PB4B-PadR6)") (class "Default")
      (node (ref "U1") (pin "R6") (pinfunction "PB4B_R6") (pintype "passive"))
    )
    (net (code "152") (name "unconnected-(U1B-PB6A-PadR7)") (class "Default")
      (node (ref "U1") (pin "R7") (pinfunction "PB6A_R7") (pintype "passive"))
    )
    (net (code "153") (name "unconnected-(U1B-PB6B-PadP7)") (class "Default")
      (node (ref "U1") (pin "P7") (pinfunction "PB6B_P7") (pintype "passive"))
    )
    (net (code "154") (name "unconnected-(U1B-PB9A-PadN7)") (class "Default")
      (node (ref "U1") (pin "N7") (pinfunction "PB9A_N7") (pintype "passive"))
    )
    (net (code "155") (name "unconnected-(U1B-PB9B-PadM7)") (class "Default")
      (node (ref "U1") (pin "M7") (pinfunction "PB9B_M7") (pintype "passive"))
    )
    (net (code "156") (name "unconnected-(U1B-PB13A-PadR8)") (class "Default")
      (node (ref "U1") (pin "R8") (pinfunction "PB13A_R8") (pintype "passive"))
    )
    (net (code "157") (name "unconnected-(U1B-PB13B-PadP8)") (class "Default")
      (node (ref "U1") (pin "P8") (pinfunction "PB13B_P8") (pintype "passive"))
    )
    (net (code "158") (name "unconnected-(U1B-PB15A-PadN8)") (class "Default")
      (node (ref "U1") (pin "N8") (pinfunction "PB15A_N8") (pintype "passive"))
    )
    (net (code "159") (name "unconnected-(U1B-PB18A-PadM9)") (class "Default")
      (node (ref "U1") (pin "M9") (pinfunction "PB18A_M9") (pintype "passive"))
    )
    (net (code "160") (name "unconnected-(U1B-PL17C-PadJ4)") (class "Default")
      (node (ref "U1") (pin "J4") (pinfunction "PL17C_J4") (pintype "passive"))
    )
    (net (code "161") (name "unconnected-(U1B-PL17D-PadJ5)") (class "Default")
      (node (ref "U1") (pin "J5") (pinfunction "PL17D_J5") (pintype "passive"))
    )
    (net (code "162") (name "unconnected-(U1B-PL20C-PadJ3)") (class "Default")
      (node (ref "U1") (pin "J3") (pinfunction "PL20C_J3") (pintype "passive"))
    )
    (net (code "163") (name "unconnected-(U1B-PL20D-PadK3)") (class "Default")
      (node (ref "U1") (pin "K3") (pinfunction "PL20D_K3") (pintype "passive"))
    )
    (net (code "164") (name "unconnected-(U1B-PL26A-PadL1)") (class "Default")
      (node (ref "U1") (pin "L1") (pinfunction "PL26A_L1") (pintype "passive"))
    )
    (net (code "165") (name "unconnected-(U1B-PL26B-PadL2)") (class "Default")
      (node (ref "U1") (pin "L2") (pinfunction "PL26B_L2") (pintype "passive"))
    )
    (net (code "166") (name "unconnected-(U1B-PL26D-PadM2)") (class "Default")
      (node (ref "U1") (pin "M2") (pinfunction "PL26D_M2") (pintype "passive"))
    )
    (net (code "167") (name "unconnected-(U1B-PL29A-PadK4)") (class "Default")
      (node (ref "U1") (pin "K4") (pinfunction "PL29A_K4") (pintype "passive"))
    )
    (net (code "168") (name "unconnected-(U1B-PL29B-PadK5)") (class "Default")
      (node (ref "U1") (pin "K5") (pinfunction "PL29B_K5") (pintype "passive"))
    )
    (net (code "169") (name "unconnected-(U1B-PL29C-PadL4)") (class "Default")
      (node (ref "U1") (pin "L4") (pinfunction "PL29C_L4") (pintype "passive"))
    )
    (net (code "170") (name "unconnected-(U1B-PL29D-PadL5)") (class "Default")
      (node (ref "U1") (pin "L5") (pinfunction "PL29D_L5") (pintype "passive"))
    )
    (net (code "171") (name "unconnected-(U1B-PL32A-PadN1)") (class "Default")
      (node (ref "U1") (pin "N1") (pinfunction "PL32A_N1") (pintype "passive"))
    )
    (net (code "172") (name "unconnected-(U1B-PL32B-PadP2)") (class "Default")
      (node (ref "U1") (pin "P2") (pinfunction "PL32B_P2") (pintype "passive"))
    )
    (net (code "173") (name "unconnected-(U1B-PL32C-PadL3)") (class "Default")
      (node (ref "U1") (pin "L3") (pinfunction "PL32C_L3") (pintype "passive"))
    )
    (net (code "174") (name "unconnected-(U1B-PL32D-PadM3)") (class "Default")
      (node (ref "U1") (pin "M3") (pinfunction "PL32D_M3") (pintype "passive"))
    )
    (net (code "175") (name "unconnected-(U1B-PL35A-PadP1)") (class "Default")
      (node (ref "U1") (pin "P1") (pinfunction "PL35A_P1") (pintype "passive"))
    )
    (net (code "176") (name "unconnected-(U1B-PL35C-PadM4)") (class "Default")
      (node (ref "U1") (pin "M4") (pinfunction "PL35C_M4") (pintype "passive"))
    )
    (net (code "177") (name "unconnected-(U1B-PL35D-PadN3)") (class "Default")
      (node (ref "U1") (pin "N3") (pinfunction "PL35D_N3") (pintype "passive"))
    )
    (net (code "178") (name "unconnected-(U1B-PL38A-PadN4)") (class "Default")
      (node (ref "U1") (pin "N4") (pinfunction "PL38A_N4") (pintype "passive"))
    )
    (net (code "179") (name "unconnected-(U1B-PL38B-PadP3)") (class "Default")
      (node (ref "U1") (pin "P3") (pinfunction "PL38B_P3") (pintype "passive"))
    )
    (net (code "180") (name "unconnected-(U1B-PL38C-PadR2)") (class "Default")
      (node (ref "U1") (pin "R2") (pinfunction "PL38C_R2") (pintype "passive"))
    )
    (net (code "181") (name "unconnected-(U1B-PL41A-PadP4)") (class "Default")
      (node (ref "U1") (pin "P4") (pinfunction "PL41A_P4") (pintype "passive"))
    )
    (net (code "182") (name "unconnected-(U1B-PL41B-PadR3)") (class "Default")
      (node (ref "U1") (pin "R3") (pinfunction "PL41B_R3") (pintype "passive"))
    )
    (net (code "183") (name "unconnected-(U1B-PL41C-PadR4)") (class "Default")
      (node (ref "U1") (pin "R4") (pinfunction "PL41C_R4") (pintype "passive"))
    )
    (net (code "184") (name "unconnected-(U1B-PL44A-PadR5)") (class "Default")
      (node (ref "U1") (pin "R5") (pinfunction "PL44A_R5") (pintype "passive"))
    )
    (net (code "185") (name "unconnected-(U1B-PL44C-PadM5)") (class "Default")
      (node (ref "U1") (pin "M5") (pinfunction "PL44C_M5") (pintype "passive"))
    )
    (net (code "186") (name "unconnected-(U1B-PL44D-PadN5)") (class "Default")
      (node (ref "U1") (pin "N5") (pinfunction "PL44D_N5") (pintype "passive"))
    )
    (net (code "187") (name "unconnected-(U1B-PL47A-PadM6)") (class "Default")
      (node (ref "U1") (pin "M6") (pinfunction "PL47A_M6") (pintype "passive"))
    )
    (net (code "188") (name "unconnected-(U1B-PL47B-PadN6)") (class "Default")
      (node (ref "U1") (pin "N6") (pinfunction "PL47B_N6") (pintype "passive"))
    )
    (net (code "189") (name "unconnected-(U1B-PL47C-PadP6)") (class "Default")
      (node (ref "U1") (pin "P6") (pinfunction "PL47C_P6") (pintype "passive"))
    )
    (net (code "190") (name "unconnected-(U1B-PL47D-PadP5)") (class "Default")
      (node (ref "U1") (pin "P5") (pinfunction "PL47D_P5") (pintype "passive"))
    )
    (net (code "191") (name "unconnected-(U1B-PR17C-PadJ13)") (class "Default")
      (node (ref "U1") (pin "J13") (pinfunction "PR17C_J13") (pintype "passive"))
    )
    (net (code "192") (name "unconnected-(U1B-PR17D-PadJ12)") (class "Default")
      (node (ref "U1") (pin "J12") (pinfunction "PR17D_J12") (pintype "passive"))
    )
    (net (code "193") (name "unconnected-(U1B-PR20C-PadJ14)") (class "Default")
      (node (ref "U1") (pin "J14") (pinfunction "PR20C_J14") (pintype "passive"))
    )
    (net (code "194") (name "unconnected-(U1B-PR20D-PadK14)") (class "Default")
      (node (ref "U1") (pin "K14") (pinfunction "PR20D_K14") (pintype "passive"))
    )
    (net (code "195") (name "unconnected-(U1B-PR23D-PadK15)") (class "Default")
      (node (ref "U1") (pin "K15") (pinfunction "PR23D_K15") (pintype "passive"))
    )
    (net (code "196") (name "unconnected-(U1B-PR26A-PadL16)") (class "Default")
      (node (ref "U1") (pin "L16") (pinfunction "PR26A_L16") (pintype "passive"))
    )
    (net (code "197") (name "unconnected-(U1B-PR29A-PadK13)") (class "Default")
      (node (ref "U1") (pin "K13") (pinfunction "PR29A_K13") (pintype "passive"))
    )
    (net (code "198") (name "unconnected-(U1B-PR29C-PadL13)") (class "Default")
      (node (ref "U1") (pin "L13") (pinfunction "PR29C_L13") (pintype "passive"))
    )
    (net (code "199") (name "unconnected-(U1B-PR32A-PadN16)") (class "Default")
      (node (ref "U1") (pin "N16") (pinfunction "PR32A_N16") (pintype "passive"))
    )
    (net (code "200") (name "unconnected-(U1B-PR32B-PadP15)") (class "Default")
      (node (ref "U1") (pin "P15") (pinfunction "PR32B_P15") (pintype "passive"))
    )
    (net (code "201") (name "unconnected-(U1B-PR32C-PadL14)") (class "Default")
      (node (ref "U1") (pin "L14") (pinfunction "PR32C_L14") (pintype "passive"))
    )
    (net (code "202") (name "unconnected-(U1B-PR35C-PadM13)") (class "Default")
      (node (ref "U1") (pin "M13") (pinfunction "PR35C_M13") (pintype "passive"))
    )
    (net (code "203") (name "unconnected-(U1B-PR35D-PadN14)") (class "Default")
      (node (ref "U1") (pin "N14") (pinfunction "PR35D_N14") (pintype "passive"))
    )
    (net (code "204") (name "unconnected-(U1B-PR38B-PadP14)") (class "Default")
      (node (ref "U1") (pin "P14") (pinfunction "PR38B_P14") (pintype "passive"))
    )
    (net (code "205") (name "unconnected-(U1B-PR41A-PadP13)") (class "Default")
      (node (ref "U1") (pin "P13") (pinfunction "PR41A_P13") (pintype "passive"))
    )
    (net (code "206") (name "unconnected-(U1B-PR41B-PadR14)") (class "Default")
      (node (ref "U1") (pin "R14") (pinfunction "PR41B_R14") (pintype "passive"))
    )
    (net (code "207") (name "unconnected-(U1B-PR44A-PadR12)") (class "Default")
      (node (ref "U1") (pin "R12") (pinfunction "PR44A_R12") (pintype "passive"))
    )
    (net (code "208") (name "unconnected-(U1B-PR44B-PadT13)") (class "Default")
      (node (ref "U1") (pin "T13") (pinfunction "PR44B_T13") (pintype "passive"))
    )
    (net (code "209") (name "unconnected-(U1B-PR44C-PadM12)") (class "Default")
      (node (ref "U1") (pin "M12") (pinfunction "PR44C_M12") (pintype "passive"))
    )
    (net (code "210") (name "unconnected-(U1B-PR44D-PadN12)") (class "Default")
      (node (ref "U1") (pin "N12") (pinfunction "PR44D_N12") (pintype "passive"))
    )
    (net (code "211") (name "unconnected-(U1B-PR47A-PadM11)") (class "Default")
      (node (ref "U1") (pin "M11") (pinfunction "PR47A_M11") (pintype "passive"))
    )
    (net (code "212") (name "unconnected-(U1B-PR47B-PadN11)") (class "Default")
      (node (ref "U1") (pin "N11") (pinfunction "PR47B_N11") (pintype "passive"))
    )
    (net (code "213") (name "unconnected-(U1B-PR47D-PadP12)") (class "Default")
      (node (ref "U1") (pin "P12") (pinfunction "PR47D_P12") (pintype "passive"))
    )
  )
)
